# Debugger.net
KiCad netlist of a schematic drawn in Altium Designer
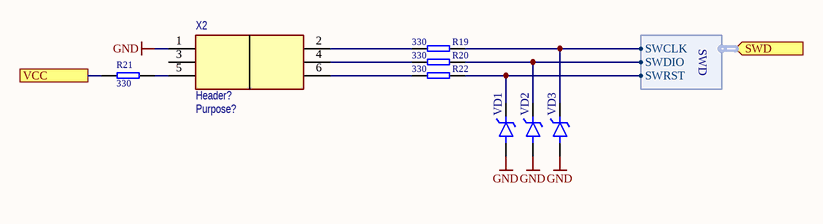
[diagram p0: Debugger.SchDoc]

(export (version "E")
  (design (tool "Eeschema 10.0.6"))
  (components
    (comp (ref "R19")
      (value "330")
      (footprint "RES 0402")
      (description "Resistor")
      (fields (field (name "Comment") "RES 0402 330"))
      (libsource (lib "!main") (part "!Resistor"))
    )
    (comp (ref "R20")
      (value "330")
      (footprint "RES 0402")
      (description "Resistor")
      (fields (field (name "Comment") "RES 0402 330"))
      (libsource (lib "!main") (part "!Resistor"))
    )
    (comp (ref "R21")
      (value "330")
      (footprint "RES 0402")
      (description "Resistor")
      (fields (field (name "Comment") "RES 0402 330"))
      (libsource (lib "!main") (part "!Resistor"))
    )
    (comp (ref "R22")
      (value "330")
      (footprint "RES 0402")
      (description "Resistor")
      (fields (field (name "Comment") "RES 0402 330"))
      (libsource (lib "!main") (part "!Resistor"))
    )
    (comp (ref "VD1")
      (value "DiodeTVSs")
      (footprint "SOD-323")
      (description "Diode TVS Single")
      (libsource (lib "diodes") (part "DiodeTVSs"))
    )
    (comp (ref "VD2")
      (value "DiodeTVSs")
      (footprint "SOD-323")
      (description "Diode TVS Single")
      (libsource (lib "diodes") (part "DiodeTVSs"))
    )
    (comp (ref "VD3")
      (value "DiodeTVSs")
      (footprint "SOD-323")
      (description "Diode TVS Single")
      (libsource (lib "diodes") (part "DiodeTVSs"))
    )
    (comp (ref "X2")
      (value "Header?")
      (footprint "PBD-6-2.54")
      (description "3x2 header")
      (fields (field (name "PURPOSE") "Purpose?"))
      (libsource (lib "connectors") (part "Header 2x3"))
    )
  )
  (nets
    (net (code "2") (name "/VCC") (class "Default")
      (node (ref "R21") (pin "2") (pinfunction "12_2") (pintype "passive"))
    )
    (net (code "4") (name "GND") (class "Default")
      (node (ref "VD1") (pin "A") (pinfunction "Anode_A") (pintype "passive"))
      (node (ref "VD2") (pin "A") (pinfunction "Anode_A") (pintype "passive"))
      (node (ref "VD3") (pin "A") (pinfunction "Anode_A") (pintype "passive"))
      (node (ref "X2") (pin "1") (pinfunction "0_1") (pintype "passive"))
    )
    (net (code "5") (name "Net-(R19-11)") (class "Default")
      (node (ref "R19") (pin "1") (pinfunction "11_1") (pintype "passive"))
      (node (ref "X2") (pin "2") (pinfunction "2_2") (pintype "passive"))
    )
    (net (code "6") (name "Net-(R19-12)") (class "Default")
      (node (ref "R19") (pin "2") (pinfunction "12_2") (pintype "passive"))
      (node (ref "VD3") (pin "C") (pinfunction "Cathode_C") (pintype "passive"))
    )
    (net (code "7") (name "Net-(R20-11)") (class "Default")
      (node (ref "R20") (pin "1") (pinfunction "11_1") (pintype "passive"))
      (node (ref "X2") (pin "4") (pinfunction "4_4") (pintype "passive"))
    )
    (net (code "8") (name "Net-(R20-12)") (class "Default")
      (node (ref "R20") (pin "2") (pinfunction "12_2") (pintype "passive"))
      (node (ref "VD2") (pin "C") (pinfunction "Cathode_C") (pintype "passive"))
    )
    (net (code "9") (name "Net-(R21-11)") (class "Default")
      (node (ref "R21") (pin "1") (pinfunction "11_1") (pintype "passive"))
      (node (ref "X2") (pin "5") (pinfunction "5_5") (pintype "passive"))
    )
    (net (code "10") (name "Net-(R22-11)") (class "Default")
      (node (ref "R22") (pin "1") (pinfunction "11_1") (pintype "passive"))
      (node (ref "X2") (pin "6") (pinfunction "6_6") (pintype "passive"))
    )
    (net (code "11") (name "Net-(R22-12)") (class "Default")
      (node (ref "R22") (pin "2") (pinfunction "12_2") (pintype "passive"))
      (node (ref "VD1") (pin "C") (pinfunction "Cathode_C") (pintype "passive"))
    )
    (net (code "12") (name "unconnected-(X2-Pad3)") (class "Default")
      (node (ref "X2") (pin "3") (pinfunction "3_3") (pintype "passive"))
    )
  )
)
